# 3_Communication.net
KiCad netlist of a schematic drawn in Altium Designer
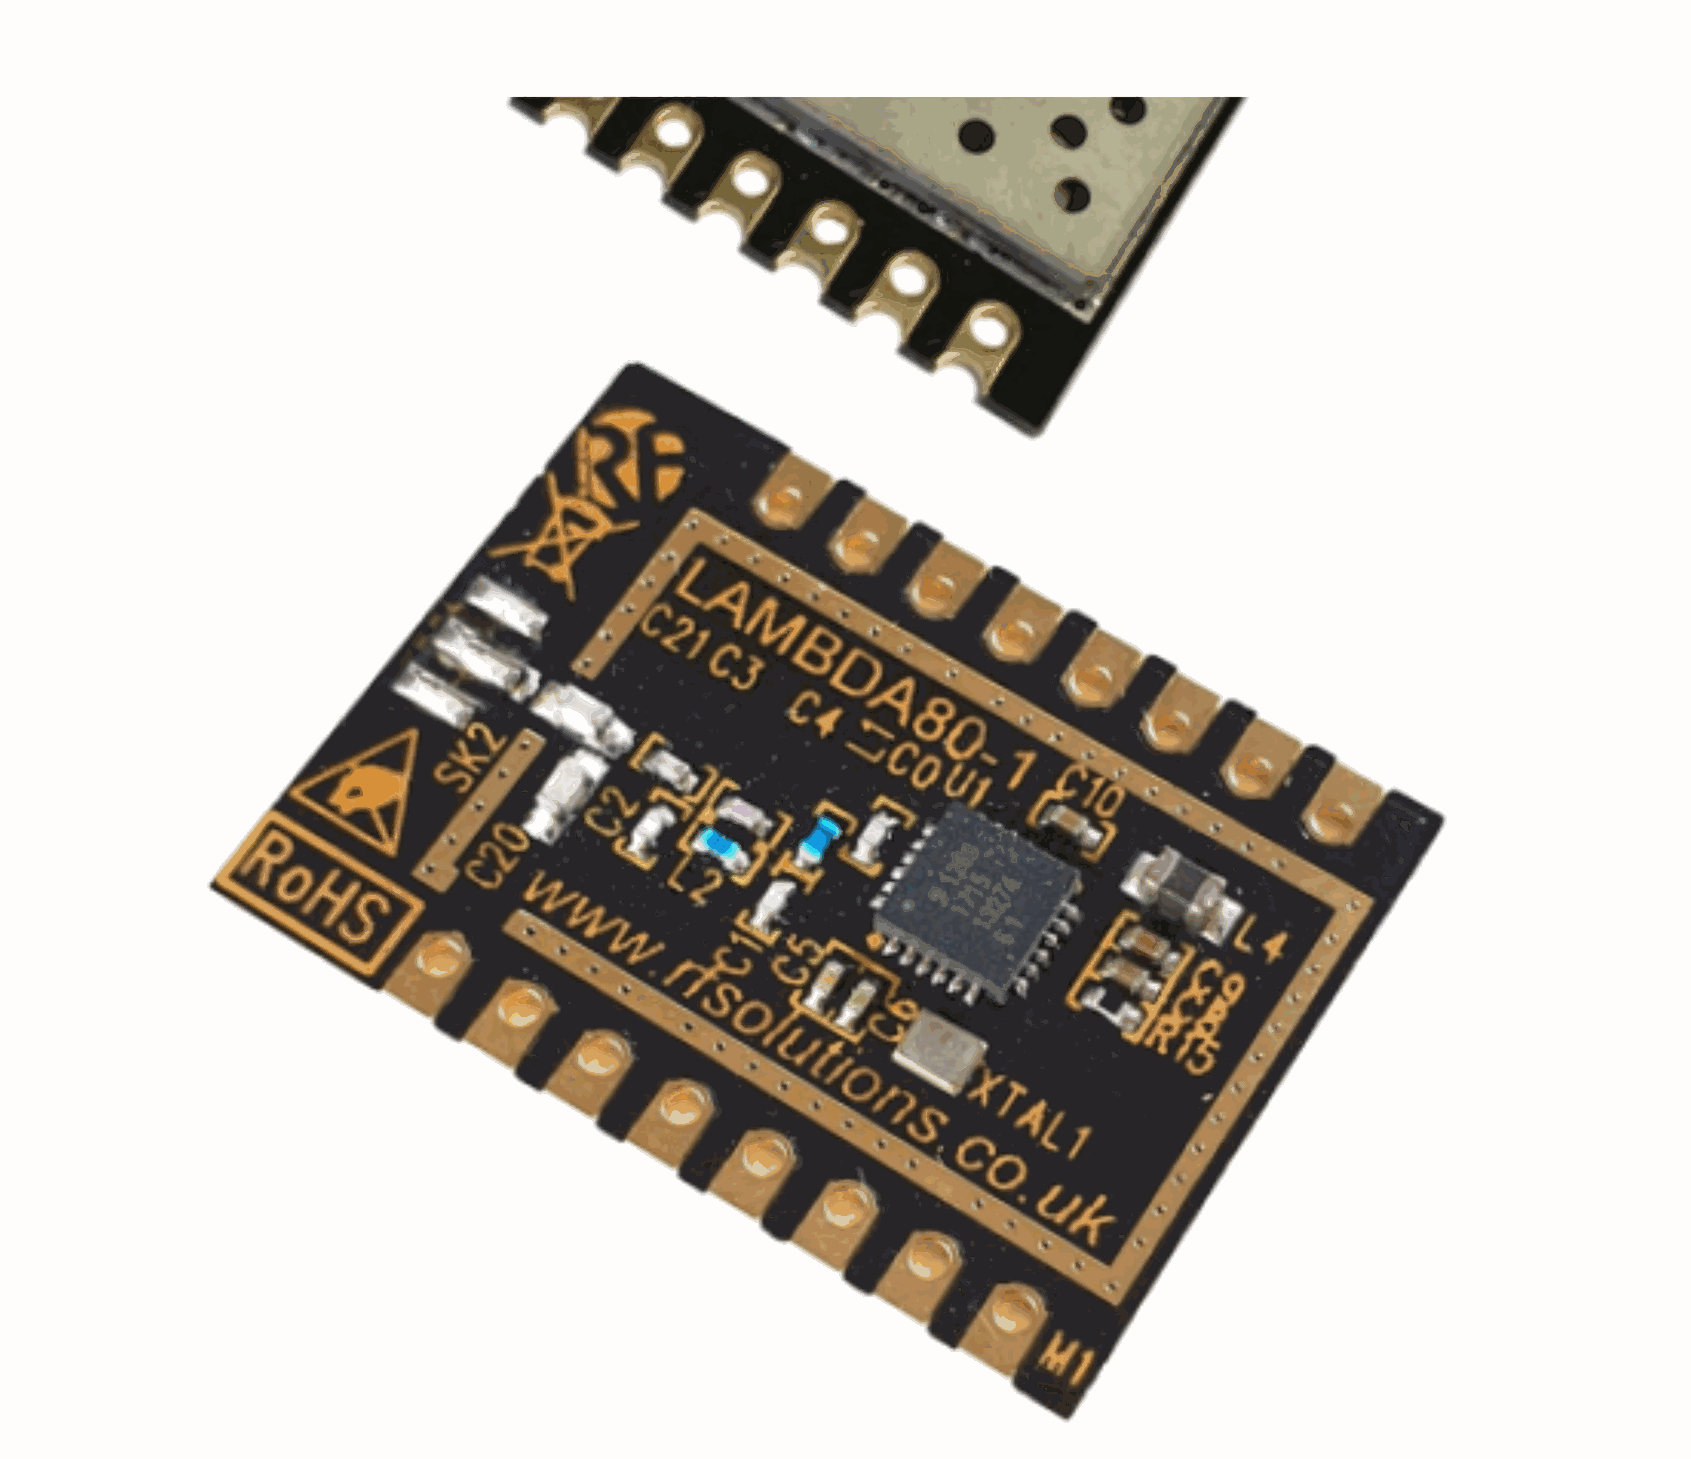
[diagram p0: 3_Communication.SchDoc, top middle]
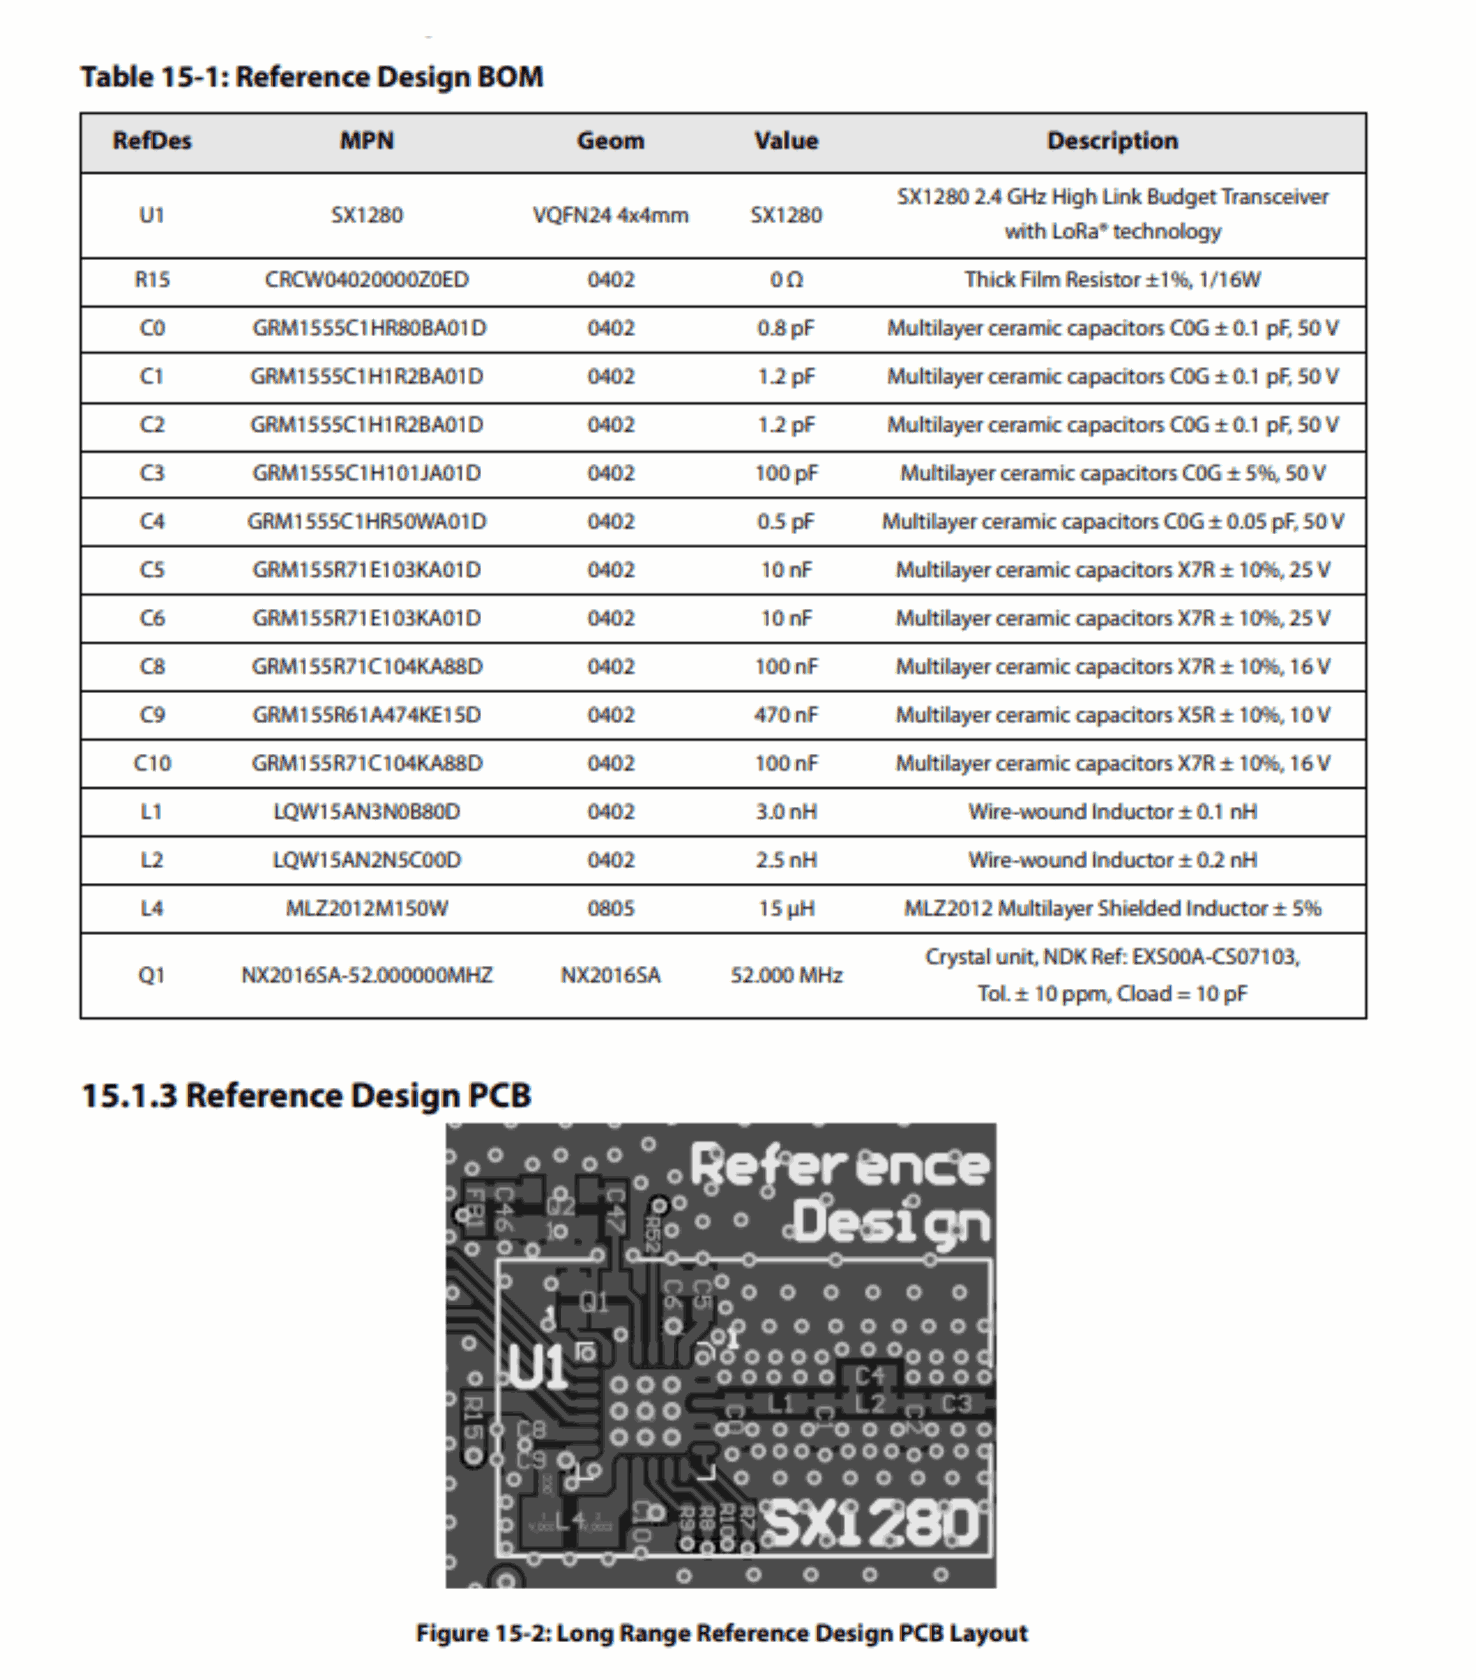
[diagram p1: 3_Communication.SchDoc, top right]
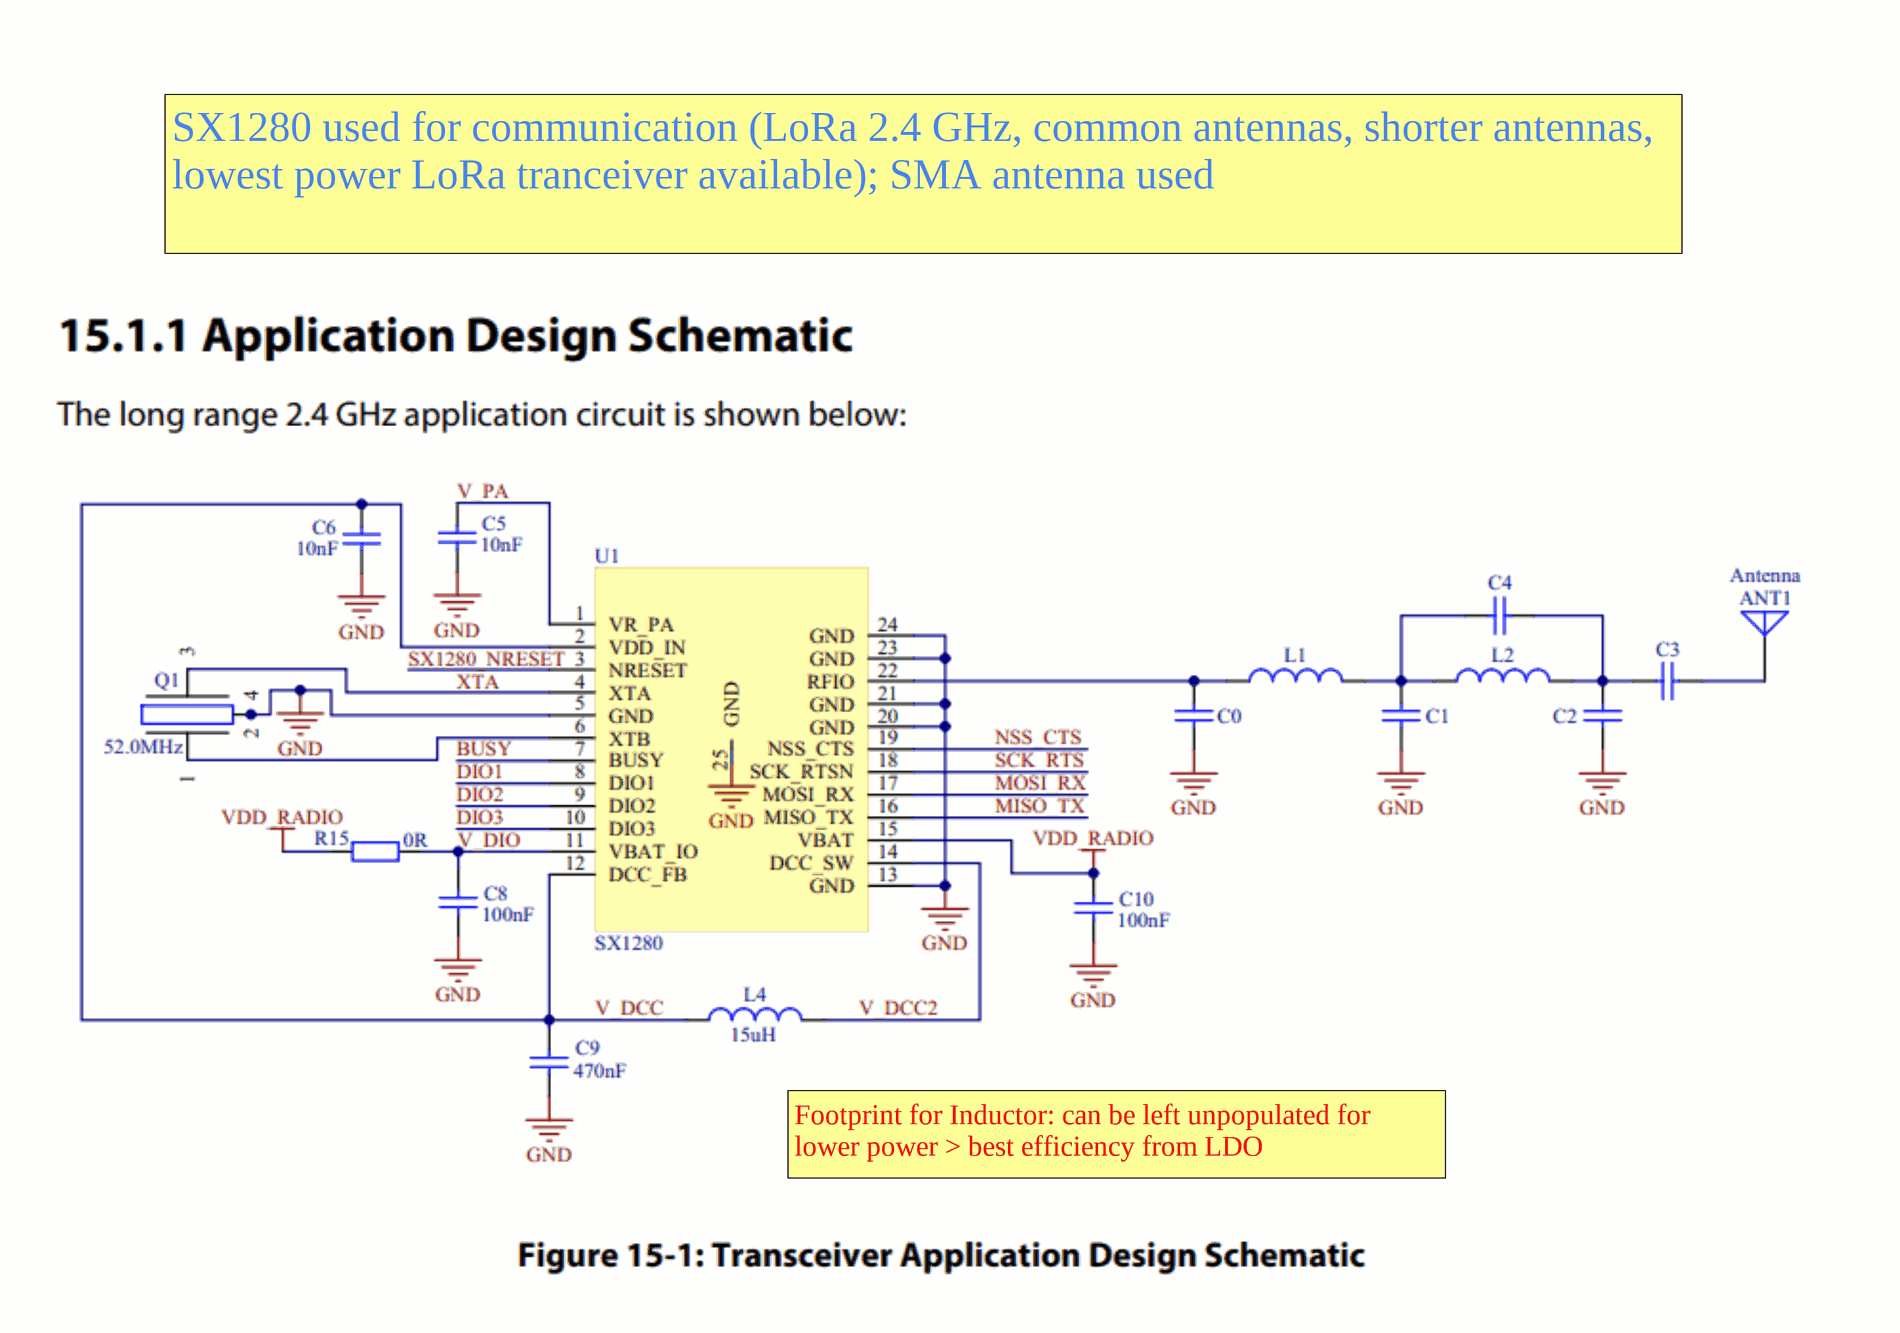
[diagram p2: 3_Communication.SchDoc, bottom left]
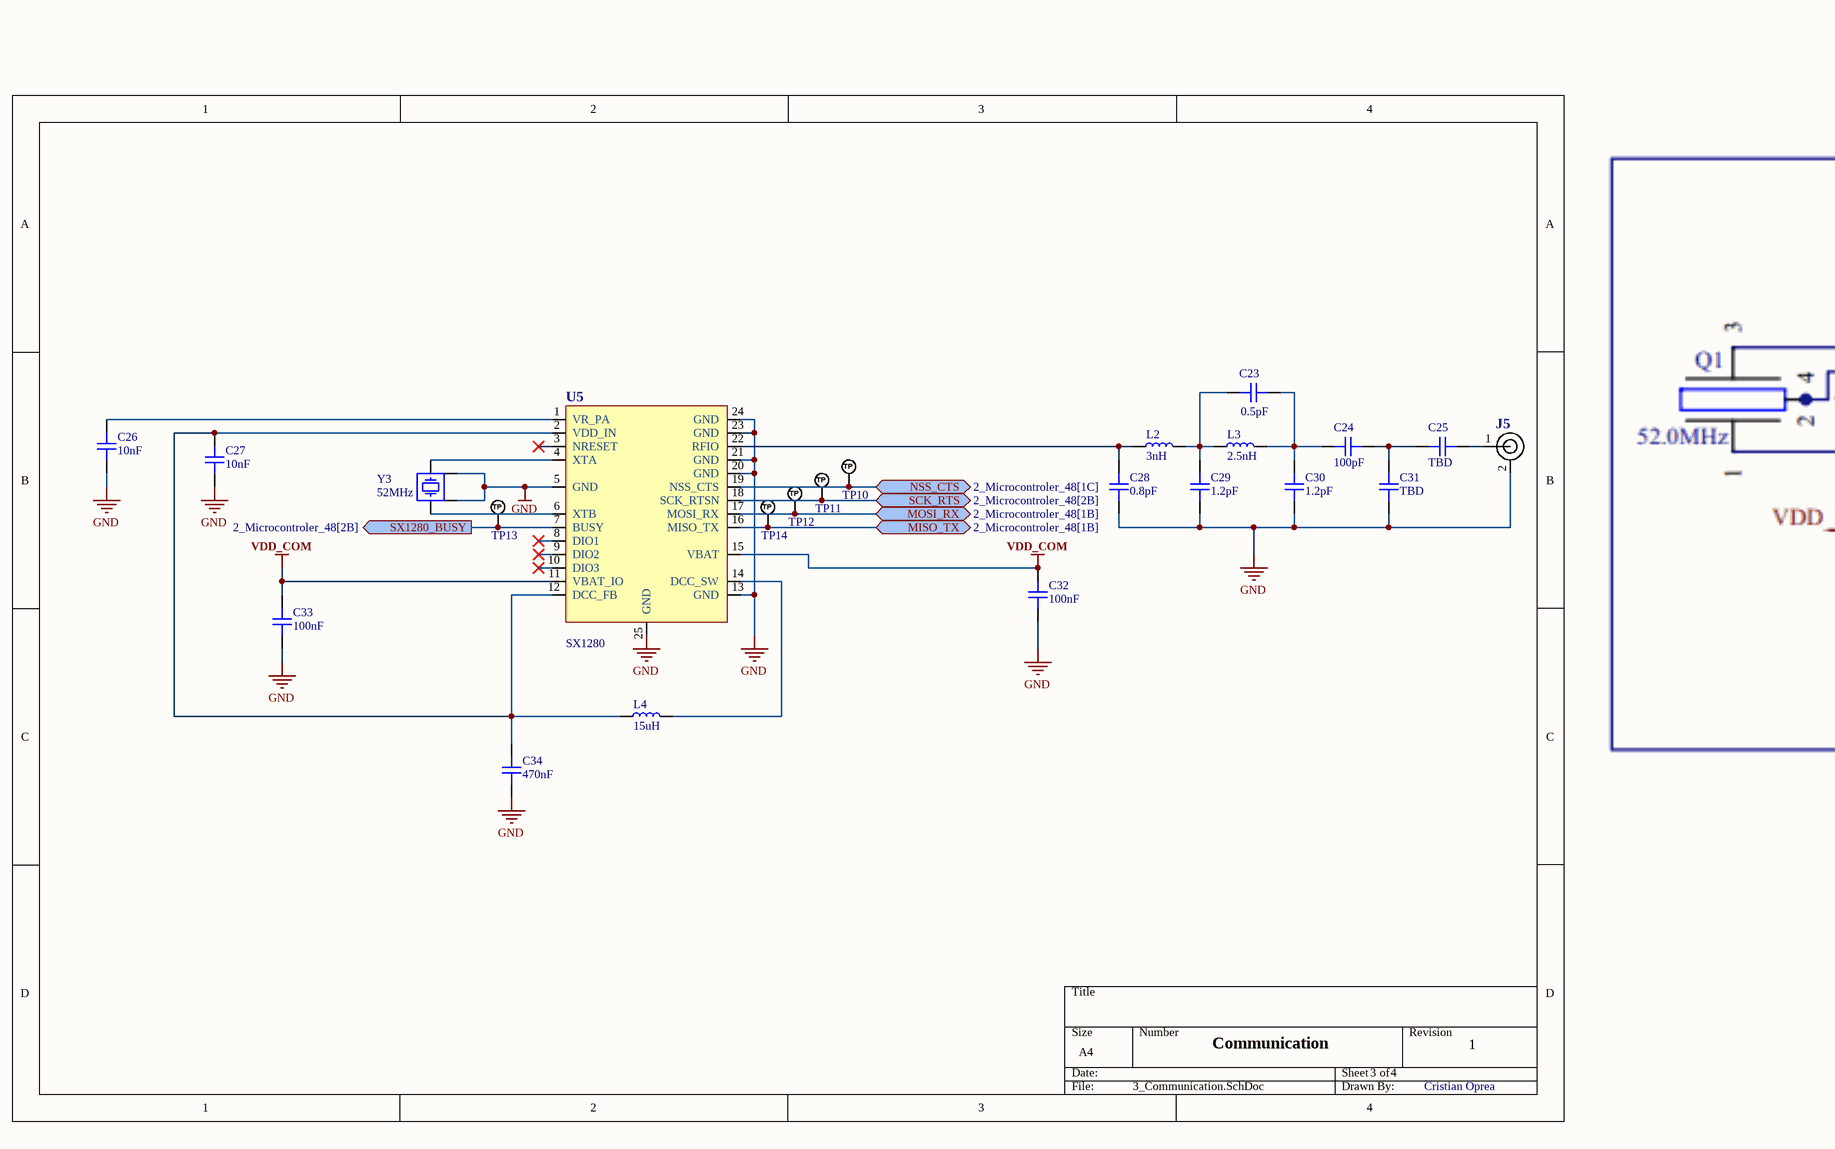
[diagram p3: 3_Communication.SchDoc, bottom middle]
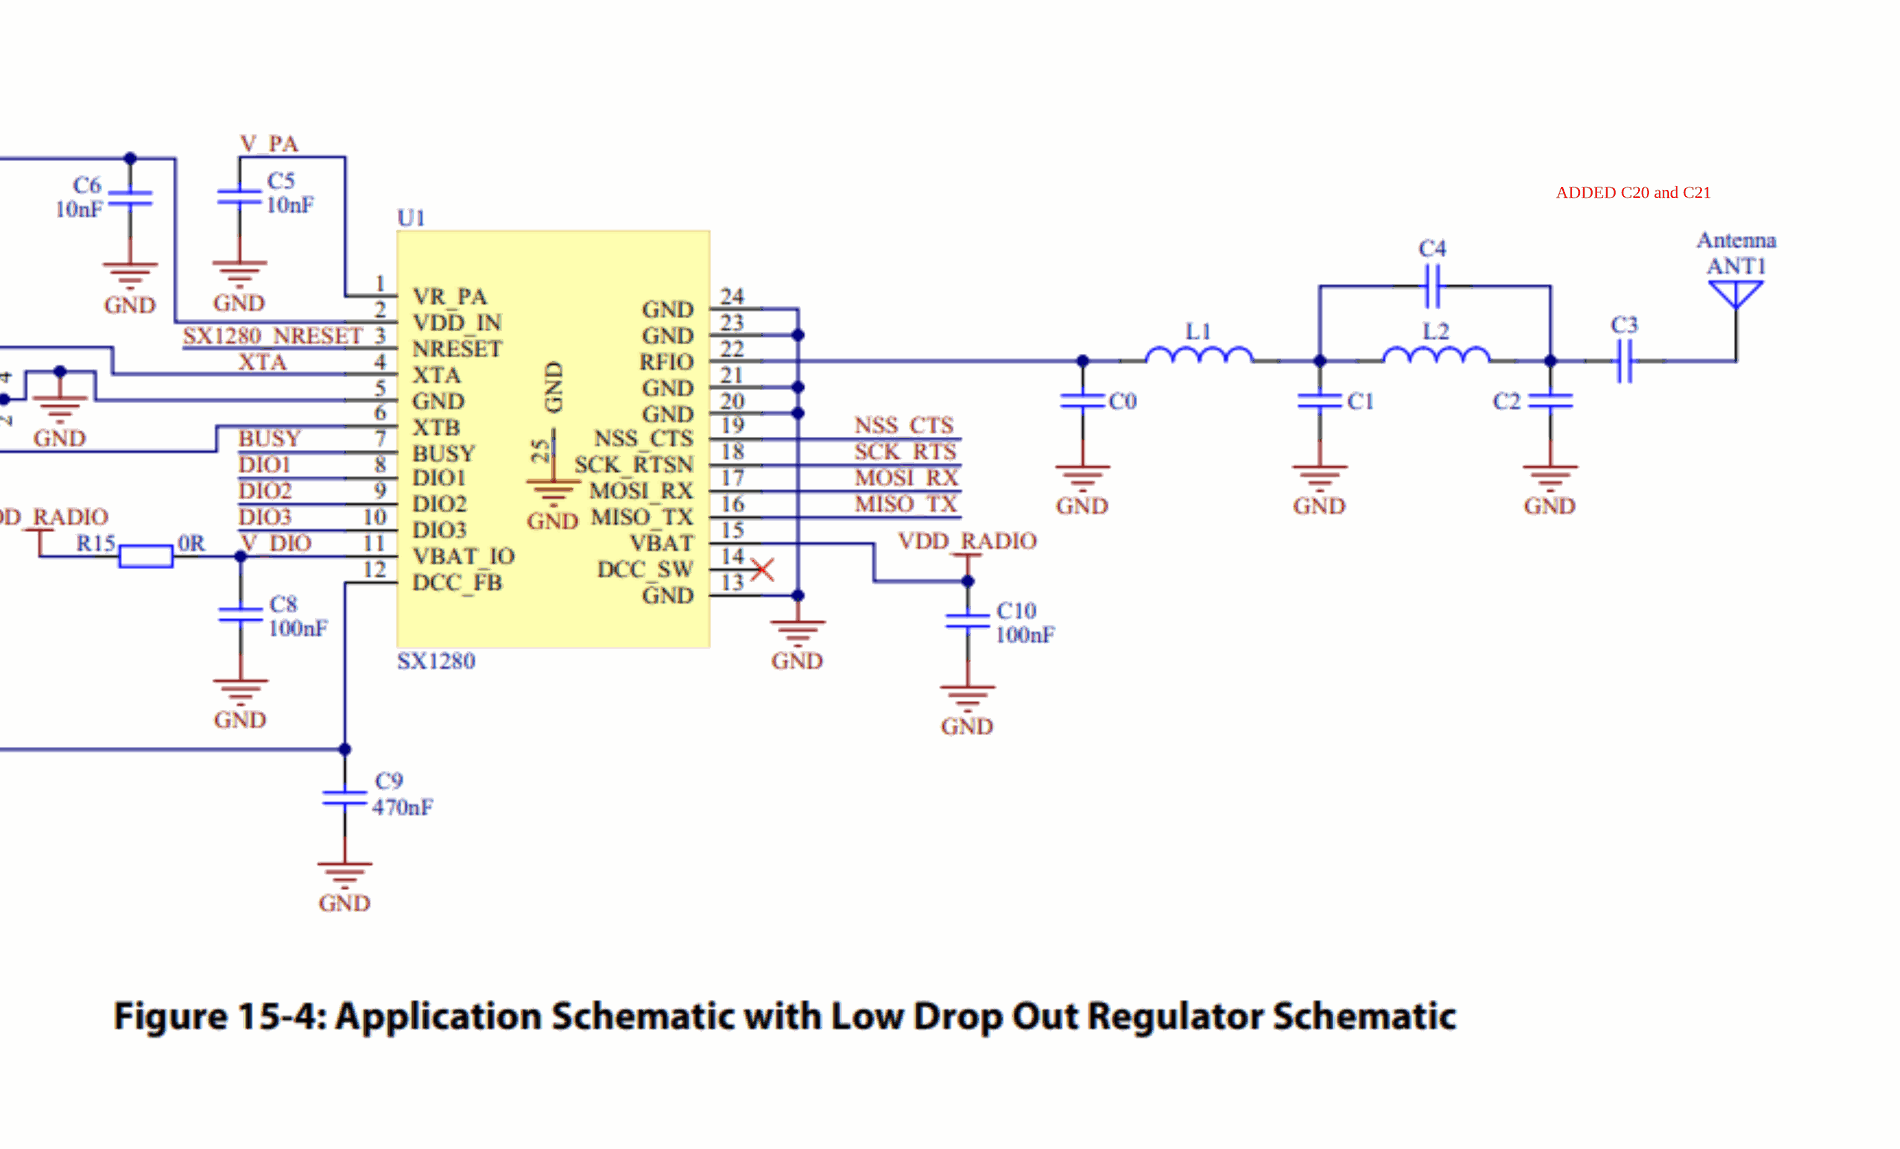
[diagram p4: 3_Communication.SchDoc, bottom right]

(export (version "E")
  (design (tool "Eeschema 10.0.6"))
  (components
    (comp (ref "C23")
      (value "0.5pF")
      (footprint "C0603")
      (description "Capacitor SMD 0603")
      (libsource (lib "Schlib_H2") (part "CAP_0603"))
    )
    (comp (ref "C24")
      (value "100pF")
      (footprint "C0603")
      (description "Capacitor SMD 0603")
      (libsource (lib "Schlib_H2") (part "CAP_0603"))
    )
    (comp (ref "C25")
      (value "TBD")
      (footprint "C0805")
      (description "Capacitor SMD 0805")
      (libsource (lib "Schlib_H2") (part "CAP_0603"))
    )
    (comp (ref "C26")
      (value "10nF")
      (footprint "C0603")
      (description "Capacitor SMD 0603")
      (libsource (lib "Schlib_H2") (part "CAP_0603"))
    )
    (comp (ref "C27")
      (value "10nF")
      (footprint "C0603")
      (description "Capacitor SMD 0603")
      (libsource (lib "Schlib_H2") (part "CAP_0603"))
    )
    (comp (ref "C28")
      (value "0.8pF")
      (footprint "C0603")
      (description "Capacitor SMD 0805")
      (libsource (lib "Schlib_H2") (part "CAP_0805"))
    )
    (comp (ref "C29")
      (value "1.2pF")
      (footprint "C0603")
      (description "Capacitor SMD 0603")
      (libsource (lib "Schlib_H2") (part "CAP_0603"))
    )
    (comp (ref "C30")
      (value "1.2pF")
      (footprint "C0603")
      (description "Capacitor SMD 0603")
      (libsource (lib "Schlib_H2") (part "CAP_0603"))
    )
    (comp (ref "C31")
      (value "TBD")
      (footprint "C0805")
      (description "Capacitor SMD 0805")
      (libsource (lib "Schlib_H2") (part "CAP_0603"))
    )
    (comp (ref "C32")
      (value "100nF")
      (footprint "C0603")
      (description "Capacitor SMD 0603")
      (libsource (lib "Schlib_H2") (part "CAP_0603"))
    )
    (comp (ref "C33")
      (value "100nF")
      (footprint "C0603")
      (description "Capacitor SMD 0603")
      (libsource (lib "Schlib_H2") (part "CAP_0603"))
    )
    (comp (ref "C34")
      (value "470nF")
      (footprint "C0603")
      (description "Capacitor SMD 0603")
      (libsource (lib "Schlib_H2") (part "CAP_0603"))
    )
    (comp (ref "J5")
      (value "SMA_EDGE_CONN")
      (footprint "CON_SMA-EDGE-S")
      (description "RF Connector SMA Female 50 Ohms 18 GHz PCB Edge Mount")
      (fields
        (field (name "MANUFACTURER") "RF Solutions")
        (field (name "MANUFACTURER PART NUMBER") "CON-SMA-EDGE-S")
      )
      (libsource (lib "Schlib_H2") (part "CON-SMA-EDGE-S"))
    )
    (comp (ref "L2")
      (value "3nH")
      (footprint "R0603")
      (description "Inductor SMD 0603")
      (libsource (lib "Schlib_H2") (part "IND_0603"))
    )
    (comp (ref "L3")
      (value "2.5nH")
      (footprint "R0603")
      (description "Inductor SMD 0603")
      (libsource (lib "Schlib_H2") (part "IND_0603"))
    )
    (comp (ref "L4")
      (value "15uH")
      (footprint "IND_3.2_4")
      (description "Inductor SMD 0603")
      (libsource (lib "Schlib_H2") (part "IND_0603"))
    )
    (comp (ref "TP10")
      (value "TP_NOBOM")
      (footprint "TEST_PAD_THD")
      (description "Test Point Round 1mm (NO BOM)")
      (libsource (lib "Schlib_H2") (part "TEST_POINT_RND_1MM"))
    )
    (comp (ref "TP11")
      (value "TP_NOBOM")
      (footprint "TEST_PAD_THD")
      (description "Test Point Round 1mm (NO BOM)")
      (libsource (lib "Schlib_H2") (part "TEST_POINT_RND_1MM"))
    )
    (comp (ref "TP12")
      (value "TP_NOBOM")
      (footprint "TEST_PAD_THD")
      (description "Test Point Round 1mm (NO BOM)")
      (libsource (lib "Schlib_H2") (part "TEST_POINT_RND_1MM"))
    )
    (comp (ref "TP13")
      (value "TP_NOBOM")
      (footprint "TEST_PAD_THD")
      (description "Test Point Round 1mm (NO BOM)")
      (libsource (lib "Schlib_H2") (part "TEST_POINT_RND_1MM"))
    )
    (comp (ref "TP14")
      (value "TP_NOBOM")
      (footprint "TEST_PAD_THD")
      (description "Test Point Round 1mm (NO BOM)")
      (libsource (lib "Schlib_H2") (part "TEST_POINT_RND_1MM"))
    )
    (comp (ref "U5")
      (value "SX1280")
      (footprint "QFN-24_4x4_0.5")
      (description "Low power LoRa transceiver operating at 2.4GHz with ranging capability")
      (libsource (lib "Schlib_H2") (part "SX1280"))
    )
    (comp (ref "Y3")
      (value "52MHz")
      (footprint "CRYSTAL_2016_4P")
      (description "Crystal")
      (fields
        (field (name "MANUFACTURER") "Epson")
        (field (name "MANUFACTURER PART NUMBER") "TSX-3225 24.0000MF15X-AC")
      )
      (libsource (lib "Schlib_H2") (part "Crystal"))
    )
  )
  (nets
    (net (code "1") (name "/MISO_TX") (class "Default")
      (node (ref "TP14") (pin "1") (pinfunction "TP_1") (pintype "passive"))
      (node (ref "U5") (pin "16") (pinfunction "MISO_TX_16") (pintype "passive"))
    )
    (net (code "2") (name "/MOSI_RX") (class "Default")
      (node (ref "TP12") (pin "1") (pinfunction "TP_1") (pintype "passive"))
      (node (ref "U5") (pin "17") (pinfunction "MOSI_RX_17") (pintype "passive"))
    )
    (net (code "3") (name "/NSS_CTS") (class "Default")
      (node (ref "TP10") (pin "1") (pinfunction "TP_1") (pintype "passive"))
      (node (ref "U5") (pin "19") (pinfunction "NSS_CTS_19") (pintype "passive"))
    )
    (net (code "4") (name "/SCK_RTS") (class "Default")
      (node (ref "TP11") (pin "1") (pinfunction "TP_1") (pintype "passive"))
      (node (ref "U5") (pin "18") (pinfunction "SCK_RTSN_18") (pintype "passive"))
    )
    (net (code "5") (name "/SX1280_BUSY") (class "Default")
      (node (ref "TP13") (pin "1") (pinfunction "TP_1") (pintype "passive"))
      (node (ref "U5") (pin "7") (pinfunction "BUSY_7") (pintype "passive"))
    )
    (net (code "6") (name "GND") (class "Default")
      (node (ref "C26") (pin "1") (pinfunction "1_1") (pintype "passive"))
      (node (ref "C27") (pin "1") (pinfunction "1_1") (pintype "passive"))
      (node (ref "C28") (pin "1") (pinfunction "1_1") (pintype "passive"))
      (node (ref "C29") (pin "1") (pinfunction "1_1") (pintype "passive"))
      (node (ref "C30") (pin "1") (pinfunction "1_1") (pintype "passive"))
      (node (ref "C31") (pin "1") (pinfunction "1_1") (pintype "passive"))
      (node (ref "C32") (pin "1") (pinfunction "1_1") (pintype "passive"))
      (node (ref "C33") (pin "1") (pinfunction "1_1") (pintype "passive"))
      (node (ref "C34") (pin "1") (pinfunction "1_1") (pintype "passive"))
      (node (ref "J5") (pin "2") (pinfunction "2_2") (pintype "passive"))
      (node (ref "U5") (pin "13") (pinfunction "GND_13") (pintype "passive"))
      (node (ref "U5") (pin "20") (pinfunction "GND_20") (pintype "passive"))
      (node (ref "U5") (pin "21") (pinfunction "GND_21") (pintype "passive"))
      (node (ref "U5") (pin "23") (pinfunction "GND_23") (pintype "passive"))
      (node (ref "U5") (pin "24") (pinfunction "GND_24") (pintype "passive"))
      (node (ref "U5") (pin "25") (pinfunction "GND_25") (pintype "passive"))
      (node (ref "U5") (pin "5") (pinfunction "GND_5") (pintype "passive"))
      (node (ref "Y3") (pin "2") (pinfunction "2_2") (pintype "passive"))
      (node (ref "Y3") (pin "4") (pinfunction "4_4") (pintype "passive"))
    )
    (net (code "7") (name "Net-(C23-Pad1)") (class "Default")
      (node (ref "C23") (pin "1") (pinfunction "1_1") (pintype "passive"))
      (node (ref "C24") (pin "2") (pinfunction "2_2") (pintype "passive"))
      (node (ref "C30") (pin "2") (pinfunction "2_2") (pintype "passive"))
      (node (ref "L3") (pin "2") (pinfunction "2_2") (pintype "passive"))
    )
    (net (code "8") (name "Net-(C23-Pad2)") (class "Default")
      (node (ref "C23") (pin "2") (pinfunction "2_2") (pintype "passive"))
      (node (ref "C29") (pin "2") (pinfunction "2_2") (pintype "passive"))
      (node (ref "L2") (pin "2") (pinfunction "2_2") (pintype "passive"))
      (node (ref "L3") (pin "1") (pinfunction "1_1") (pintype "passive"))
    )
    (net (code "9") (name "Net-(C24-Pad1)") (class "Default")
      (node (ref "C24") (pin "1") (pinfunction "1_1") (pintype "passive"))
      (node (ref "C25") (pin "2") (pinfunction "2_2") (pintype "passive"))
      (node (ref "C31") (pin "2") (pinfunction "2_2") (pintype "passive"))
    )
    (net (code "10") (name "Net-(C25-Pad1)") (class "Default")
      (node (ref "C25") (pin "1") (pinfunction "1_1") (pintype "passive"))
      (node (ref "J5") (pin "1") (pinfunction "1_1") (pintype "passive"))
    )
    (net (code "11") (name "Net-(U5-DCC_FB)") (class "Default")
      (node (ref "C27") (pin "2") (pinfunction "2_2") (pintype "passive"))
      (node (ref "C34") (pin "2") (pinfunction "2_2") (pintype "passive"))
      (node (ref "L4") (pin "1") (pinfunction "1_1") (pintype "passive"))
      (node (ref "U5") (pin "12") (pinfunction "DCC_FB_12") (pintype "passive"))
      (node (ref "U5") (pin "2") (pinfunction "VDD_IN_2") (pintype "passive"))
    )
    (net (code "12") (name "Net-(U5-DCC_SW)") (class "Default")
      (node (ref "L4") (pin "2") (pinfunction "2_2") (pintype "passive"))
      (node (ref "U5") (pin "14") (pinfunction "DCC_SW_14") (pintype "passive"))
    )
    (net (code "13") (name "Net-(U5-RFIO)") (class "Default")
      (node (ref "C28") (pin "2") (pinfunction "2_2") (pintype "passive"))
      (node (ref "L2") (pin "1") (pinfunction "1_1") (pintype "passive"))
      (node (ref "U5") (pin "22") (pinfunction "RFIO_22") (pintype "passive"))
    )
    (net (code "14") (name "Net-(U5-VR_PA)") (class "Default")
      (node (ref "C26") (pin "2") (pinfunction "2_2") (pintype "passive"))
      (node (ref "U5") (pin "1") (pinfunction "VR_PA_1") (pintype "passive"))
    )
    (net (code "15") (name "Net-(U5-XTA)") (class "Default")
      (node (ref "U5") (pin "4") (pinfunction "XTA_4") (pintype "passive"))
      (node (ref "Y3") (pin "3") (pinfunction "3_3") (pintype "passive"))
    )
    (net (code "16") (name "Net-(U5-XTB)") (class "Default")
      (node (ref "U5") (pin "6") (pinfunction "XTB_6") (pintype "passive"))
      (node (ref "Y3") (pin "1") (pinfunction "1_1") (pintype "passive"))
    )
    (net (code "17") (name "VDD_COM") (class "Default")
      (node (ref "C32") (pin "2") (pinfunction "2_2") (pintype "passive"))
      (node (ref "C33") (pin "2") (pinfunction "2_2") (pintype "passive"))
      (node (ref "U5") (pin "11") (pinfunction "VBAT_IO_11") (pintype "passive"))
      (node (ref "U5") (pin "15") (pinfunction "VBAT_15") (pintype "passive"))
    )
    (net (code "18") (name "unconnected-(U5-DIO1-Pad8)") (class "Default")
      (node (ref "U5") (pin "8") (pinfunction "DIO1_8") (pintype "passive+no_connect"))
    )
    (net (code "19") (name "unconnected-(U5-DIO2-Pad9)") (class "Default")
      (node (ref "U5") (pin "9") (pinfunction "DIO2_9") (pintype "passive+no_connect"))
    )
    (net (code "20") (name "unconnected-(U5-DIO3-Pad10)") (class "Default")
      (node (ref "U5") (pin "10") (pinfunction "DIO3_10") (pintype "passive+no_connect"))
    )
    (net (code "21") (name "unconnected-(U5-NRESET-Pad3)") (class "Default")
      (node (ref "U5") (pin "3") (pinfunction "NRESET_3") (pintype "passive+no_connect"))
    )
  )
)
